# I2C_Temperature_Sensor.net
KiCad netlist of a schematic drawn in Altium Designer
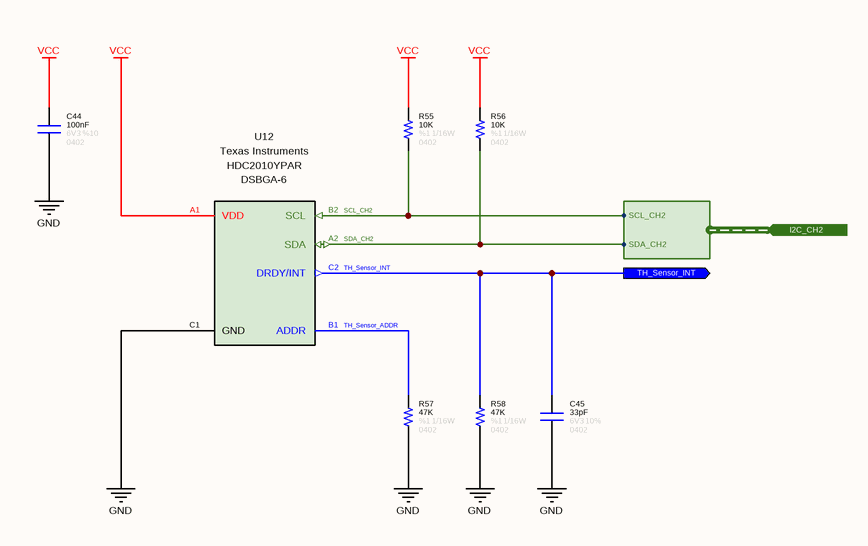
[diagram p0: I2C Temperature Sensor.SchDoc]

(export (version "E")
  (design (tool "Eeschema 10.0.6"))
  (components
    (comp (ref "C44")
      (value "100nF")
      (footprint "CAPACITOR_0402")
      (description "Capacitor - 100nF [0402-6V3] (Ceramic)")
      (fields
        (field (name "MANUFACTURER PART NUMBER") "04026D104KAT4A")
        (field (name "TOLERANCE") "%10")
        (field (name "VOLTAGE") "6V3")
        (field (name "CASE") "0402")
        (field (name "Comment") "Capacitor - 100nF [0402] (Ceramic)")
      )
      (libsource (lib "P101DA_Library") (part "Capacitor - 100nF [0402-6V3]"))
    )
    (comp (ref "C45")
      (value "33pF")
      (footprint "CAPACITOR_0402")
      (description "Capacitor - 33pF [0402] (Ceramic)")
      (fields
        (field (name "MANUFACTURER PART NUMBER") "C0402C330J9RACAUTO")
        (field (name "TOLERANCE") "10%")
        (field (name "CASE") "0402")
        (field (name "VOLTAGE") "6V3")
      )
      (libsource (lib "P101DA_Library") (part "Capacitor - 33pF [0402-6V3]"))
    )
    (comp (ref "R55")
      (value "10K")
      (footprint "RESISTOR_0402")
      (description "Thick Film Resistors - SMD 1/16 W 10 KOhm 1%")
      (fields
        (field (name "MANUFACTURER PART NUMBER") "CRCW040210K0FKED")
        (field (name "TOLERANCE") "%1")
        (field (name "CASE") "0402")
        (field (name "POWER") "1/16W")
        (field (name "Comment") "10K - 0402 - %1 - 1/16W")
      )
      (libsource (lib "P101DA_Library") (part "Resistor - 10K [0402]"))
    )
    (comp (ref "R56")
      (value "10K")
      (footprint "RESISTOR_0402")
      (description "Thick Film Resistors - SMD 1/16 W 10 KOhm 1%")
      (fields
        (field (name "MANUFACTURER PART NUMBER") "CRCW040210K0FKED")
        (field (name "TOLERANCE") "%1")
        (field (name "CASE") "0402")
        (field (name "POWER") "1/16W")
        (field (name "Comment") "10K - 0402 - %1 - 1/16W")
      )
      (libsource (lib "P101DA_Library") (part "Resistor - 10K [0402]"))
    )
    (comp (ref "R57")
      (value "47K")
      (footprint "RESISTOR_0402")
      (description "Thick Film Resistors - SMD 1/16 W 47 KOhm 1%")
      (fields
        (field (name "MANUFACTURER PART NUMBER") "CRCW040247K0FKED")
        (field (name "TOLERANCE") "%1")
        (field (name "CASE") "0402")
        (field (name "POWER") "1/16W")
        (field (name "Comment") "47K - 0402 - %1 - 1/16W")
      )
      (libsource (lib "P101DA_Library") (part "Resistor - 47K [0402]"))
    )
    (comp (ref "R58")
      (value "47K")
      (footprint "RESISTOR_0402")
      (description "Thick Film Resistors - SMD 1/16 W 47 KOhm 1%")
      (fields
        (field (name "MANUFACTURER PART NUMBER") "CRCW040247K0FKED")
        (field (name "TOLERANCE") "%1")
        (field (name "CASE") "0402")
        (field (name "POWER") "1/16W")
        (field (name "Comment") "47K - 0402 - %1 - 1/16W")
      )
      (libsource (lib "P101DA_Library") (part "Resistor - 47K [0402]"))
    )
    (comp (ref "U12")
      (value "HDC2010YPAR")
      (footprint "HDC2010")
      (description "GEN 2 HUMIDITY SENSOR")
      (fields
        (field (name "MANUFACTURER NAME") "Texas Instruments")
        (field (name "MANUFACTURER PART NUMBER") "HDC2010YPAR")
        (field (name "CASE") "DSBGA-6")
      )
      (libsource (lib "P101DA_Library") (part "IC - HDC2010"))
    )
  )
  (nets
    (net (code "2") (name "/SCL_CH2") (class "Default")
      (node (ref "R55") (pin "1") (pinfunction "1_1") (pintype "passive"))
      (node (ref "U12") (pin "B2") (pinfunction "SCL_B2") (pintype "input"))
    )
    (net (code "3") (name "/SDA_CH2") (class "Default")
      (node (ref "R56") (pin "1") (pinfunction "1_1") (pintype "passive"))
      (node (ref "U12") (pin "A2") (pinfunction "SDA_A2") (pintype "bidirectional"))
    )
    (net (code "4") (name "/TH_Sensor_ADDR") (class "Default")
      (node (ref "R57") (pin "2") (pinfunction "2_2") (pintype "passive"))
      (node (ref "U12") (pin "B1") (pinfunction "ADDR_B1") (pintype "passive"))
    )
    (net (code "5") (name "/TH_Sensor_INT") (class "Default")
      (node (ref "C45") (pin "2") (pinfunction "2_2") (pintype "passive"))
      (node (ref "R58") (pin "2") (pinfunction "2_2") (pintype "passive"))
      (node (ref "U12") (pin "C2") (pinfunction "DRDY/INT_C2") (pintype "output"))
    )
    (net (code "7") (name "GND") (class "Default")
      (node (ref "C44") (pin "1") (pinfunction "1_1") (pintype "passive"))
      (node (ref "C45") (pin "1") (pinfunction "1_1") (pintype "passive"))
      (node (ref "R57") (pin "1") (pinfunction "1_1") (pintype "passive"))
      (node (ref "R58") (pin "1") (pinfunction "1_1") (pintype "passive"))
      (node (ref "U12") (pin "C1") (pinfunction "GND_C1") (pintype "power_in"))
    )
    (net (code "8") (name "VCC") (class "Default")
      (node (ref "C44") (pin "2") (pinfunction "2_2") (pintype "passive"))
      (node (ref "R55") (pin "2") (pinfunction "2_2") (pintype "passive"))
      (node (ref "R56") (pin "2") (pinfunction "2_2") (pintype "passive"))
      (node (ref "U12") (pin "A1") (pinfunction "VDD_A1") (pintype "power_in"))
    )
  )
)
